# power.net
KiCad netlist of a schematic drawn in Altium Designer
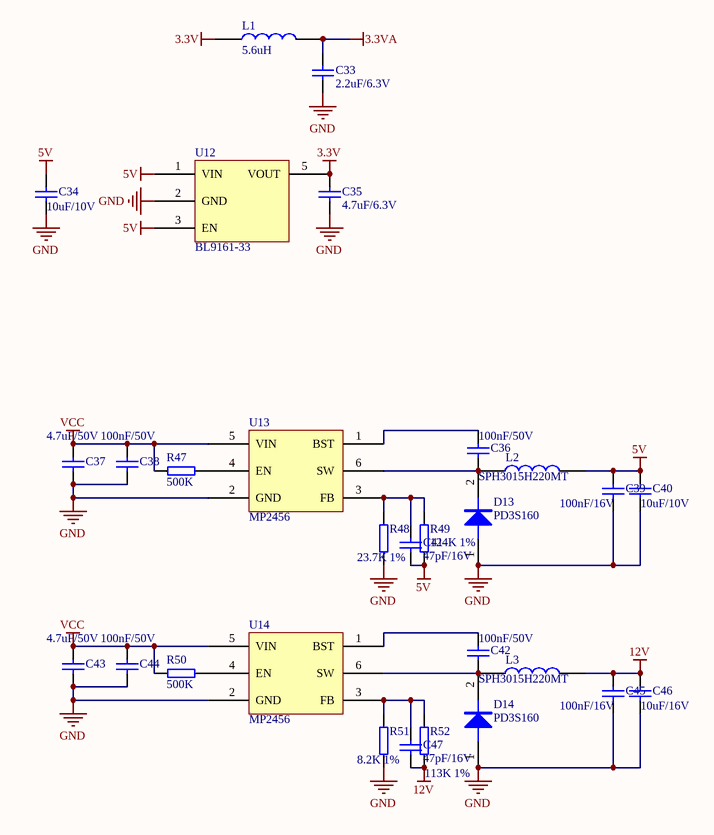
[diagram p0: power.SchDoc]

(export (version "E")
  (design (tool "Eeschema 10.0.6"))
  (components
    (comp (ref "C33") (value "2.2uF/6.3V") (footprint "C0402") (libsource (lib "zijianku") (part "cap")))
    (comp (ref "C34") (value "10uF/10V") (footprint "C0603") (libsource (lib "zijianku") (part "cap")))
    (comp (ref "C35") (value "4.7uF/6.3V") (footprint "C0603") (libsource (lib "zijianku") (part "cap")))
    (comp (ref "C36") (value "100nF/50V") (footprint "C0402") (libsource (lib "zijianku") (part "cap")))
    (comp (ref "C37") (value "4.7uF/50V") (footprint "C0603") (libsource (lib "zijianku") (part "cap")))
    (comp (ref "C38") (value "100nF/50V") (footprint "C0402") (libsource (lib "zijianku") (part "cap")))
    (comp (ref "C39") (value "100nF/16V") (footprint "C0402") (libsource (lib "zijianku") (part "cap")))
    (comp (ref "C40") (value "10uF/10V") (footprint "C0603") (libsource (lib "zijianku") (part "cap")))
    (comp (ref "C41") (value "47pF/16V") (footprint "C0402") (libsource (lib "zijianku") (part "cap")))
    (comp (ref "C42") (value "100nF/50V") (footprint "C0402") (libsource (lib "zijianku") (part "cap")))
    (comp (ref "C43") (value "4.7uF/50V") (footprint "C0603") (libsource (lib "zijianku") (part "cap")))
    (comp (ref "C44") (value "100nF/50V") (footprint "C0402") (libsource (lib "zijianku") (part "cap")))
    (comp (ref "C45") (value "100nF/16V") (footprint "C0402") (libsource (lib "zijianku") (part "cap")))
    (comp (ref "C46") (value "10uF/16V") (footprint "C0805") (libsource (lib "zijianku") (part "cap")))
    (comp (ref "C47") (value "47pF/16V") (footprint "C0402") (libsource (lib "zijianku") (part "cap")))
    (comp (ref "D13") (value "PD3S160") (footprint "POWERDI323") (libsource (lib "*") (part "DIODE")))
    (comp (ref "D14") (value "PD3S160") (footprint "POWERDI323") (libsource (lib "*") (part "DIODE")))
    (comp (ref "L1")
      (value "5.6uH")
      (footprint "L0402")
      (description "贴片电感")
      (libsource (lib "zijianku") (part "INDUCTOR"))
    )
    (comp (ref "L2")
      (value "SPH3015H220MT")
      (footprint "SPH3015")
      (description "顺络 22uH")
      (libsource (lib "zijianku") (part "INDUCTOR"))
    )
    (comp (ref "L3")
      (value "SPH3015H220MT")
      (footprint "SPH3015")
      (description "顺络 22uH")
      (libsource (lib "zijianku") (part "INDUCTOR"))
    )
    (comp (ref "R47") (value "500K") (footprint "R0402") (libsource (lib "zijianku") (part "Resistance")))
    (comp (ref "R48") (value "23.7K 1%") (footprint "R0402") (libsource (lib "zijianku") (part "Resistance")))
    (comp (ref "R49") (value "124K 1%") (footprint "R0402") (libsource (lib "zijianku") (part "Resistance")))
    (comp (ref "R50") (value "500K") (footprint "R0402") (libsource (lib "zijianku") (part "Resistance")))
    (comp (ref "R51") (value "8.2K 1%") (footprint "R0402") (libsource (lib "zijianku") (part "Resistance")))
    (comp (ref "R52") (value "113K 1%") (footprint "R0402") (libsource (lib "zijianku") (part "Resistance")))
    (comp (ref "U12")
      (value "BL9161-33")
      (footprint "SOT-23(5)")
      (libsource (lib "zijianku") (part "BL9161"))
    )
    (comp (ref "U13") (value "MP2456") (footprint "SOT-23(6)") (libsource (lib "zijianku") (part "MP2456")))
    (comp (ref "U14") (value "MP2456") (footprint "SOT-23(6)") (libsource (lib "zijianku") (part "MP2456")))
  )
  (nets
    (net (code "1") (name "3.3V") (class "Default")
      (node (ref "C35") (pin "2") (pinfunction "1_2") (pintype "passive"))
      (node (ref "L1") (pin "1") (pinfunction "1_1") (pintype "passive"))
      (node (ref "U12") (pin "5") (pinfunction "VOUT_5") (pintype "passive"))
    )
    (net (code "2") (name "3.3VA") (class "Default")
      (node (ref "C33") (pin "2") (pinfunction "1_2") (pintype "passive"))
      (node (ref "L1") (pin "2") (pinfunction "2_2") (pintype "passive"))
    )
    (net (code "3") (name "5V") (class "Default")
      (node (ref "C34") (pin "2") (pinfunction "1_2") (pintype "passive"))
      (node (ref "C39") (pin "2") (pinfunction "1_2") (pintype "passive"))
      (node (ref "C40") (pin "2") (pinfunction "1_2") (pintype "passive"))
      (node (ref "C41") (pin "2") (pinfunction "1_2") (pintype "passive"))
      (node (ref "L2") (pin "2") (pinfunction "2_2") (pintype "passive"))
      (node (ref "R49") (pin "1") (pintype "passive"))
      (node (ref "U12") (pin "1") (pinfunction "VIN_1") (pintype "passive"))
      (node (ref "U12") (pin "3") (pinfunction "EN_3") (pintype "passive"))
    )
    (net (code "4") (name "12V") (class "Default")
      (node (ref "C45") (pin "2") (pinfunction "1_2") (pintype "passive"))
      (node (ref "C46") (pin "2") (pinfunction "1_2") (pintype "passive"))
      (node (ref "C47") (pin "2") (pinfunction "1_2") (pintype "passive"))
      (node (ref "L3") (pin "2") (pinfunction "2_2") (pintype "passive"))
      (node (ref "R52") (pin "1") (pintype "passive"))
    )
    (net (code "5") (name "GND") (class "Default")
      (node (ref "C33") (pin "1") (pinfunction "0_1") (pintype "passive"))
      (node (ref "C34") (pin "1") (pinfunction "0_1") (pintype "passive"))
      (node (ref "C35") (pin "1") (pinfunction "0_1") (pintype "passive"))
      (node (ref "C37") (pin "1") (pinfunction "0_1") (pintype "passive"))
      (node (ref "C38") (pin "1") (pinfunction "0_1") (pintype "passive"))
      (node (ref "C39") (pin "1") (pinfunction "0_1") (pintype "passive"))
      (node (ref "C40") (pin "1") (pinfunction "0_1") (pintype "passive"))
      (node (ref "C43") (pin "1") (pinfunction "0_1") (pintype "passive"))
      (node (ref "C44") (pin "1") (pinfunction "0_1") (pintype "passive"))
      (node (ref "C45") (pin "1") (pinfunction "0_1") (pintype "passive"))
      (node (ref "C46") (pin "1") (pinfunction "0_1") (pintype "passive"))
      (node (ref "D13") (pin "1") (pinfunction "A_1") (pintype "passive"))
      (node (ref "D14") (pin "1") (pinfunction "A_1") (pintype "passive"))
      (node (ref "R48") (pin "1") (pintype "passive"))
      (node (ref "R51") (pin "1") (pintype "passive"))
      (node (ref "U12") (pin "2") (pinfunction "GND_2") (pintype "passive"))
      (node (ref "U13") (pin "2") (pinfunction "GND_2") (pintype "passive"))
      (node (ref "U14") (pin "2") (pinfunction "GND_2") (pintype "passive"))
    )
    (net (code "6") (name "Net-(C36-0)") (class "Default")
      (node (ref "C36") (pin "1") (pinfunction "0_1") (pintype "passive"))
      (node (ref "U13") (pin "1") (pinfunction "BST_1") (pintype "passive"))
    )
    (net (code "7") (name "Net-(C36-1)") (class "Default")
      (node (ref "C36") (pin "2") (pinfunction "1_2") (pintype "passive"))
      (node (ref "D13") (pin "2") (pinfunction "K_2") (pintype "passive"))
      (node (ref "L2") (pin "1") (pinfunction "1_1") (pintype "passive"))
      (node (ref "U13") (pin "6") (pinfunction "SW_6") (pintype "passive"))
    )
    (net (code "8") (name "Net-(C41-0)") (class "Default")
      (node (ref "C41") (pin "1") (pinfunction "0_1") (pintype "passive"))
      (node (ref "R48") (pin "2") (pintype "passive"))
      (node (ref "R49") (pin "2") (pintype "passive"))
      (node (ref "U13") (pin "3") (pinfunction "FB_3") (pintype "passive"))
    )
    (net (code "9") (name "Net-(C42-0)") (class "Default")
      (node (ref "C42") (pin "1") (pinfunction "0_1") (pintype "passive"))
      (node (ref "U14") (pin "1") (pinfunction "BST_1") (pintype "passive"))
    )
    (net (code "10") (name "Net-(C42-1)") (class "Default")
      (node (ref "C42") (pin "2") (pinfunction "1_2") (pintype "passive"))
      (node (ref "D14") (pin "2") (pinfunction "K_2") (pintype "passive"))
      (node (ref "L3") (pin "1") (pinfunction "1_1") (pintype "passive"))
      (node (ref "U14") (pin "6") (pinfunction "SW_6") (pintype "passive"))
    )
    (net (code "11") (name "Net-(C47-0)") (class "Default")
      (node (ref "C47") (pin "1") (pinfunction "0_1") (pintype "passive"))
      (node (ref "R51") (pin "2") (pintype "passive"))
      (node (ref "R52") (pin "2") (pintype "passive"))
      (node (ref "U14") (pin "3") (pinfunction "FB_3") (pintype "passive"))
    )
    (net (code "12") (name "Net-(U13-EN)") (class "Default")
      (node (ref "R47") (pin "2") (pintype "passive"))
      (node (ref "U13") (pin "4") (pinfunction "EN_4") (pintype "passive"))
    )
    (net (code "13") (name "Net-(U14-EN)") (class "Default")
      (node (ref "R50") (pin "2") (pintype "passive"))
      (node (ref "U14") (pin "4") (pinfunction "EN_4") (pintype "passive"))
    )
    (net (code "14") (name "VCC") (class "Default")
      (node (ref "C37") (pin "2") (pinfunction "1_2") (pintype "passive"))
      (node (ref "C38") (pin "2") (pinfunction "1_2") (pintype "passive"))
      (node (ref "C43") (pin "2") (pinfunction "1_2") (pintype "passive"))
      (node (ref "C44") (pin "2") (pinfunction "1_2") (pintype "passive"))
      (node (ref "R47") (pin "1") (pintype "passive"))
      (node (ref "R50") (pin "1") (pintype "passive"))
      (node (ref "U13") (pin "5") (pinfunction "VIN_5") (pintype "passive"))
      (node (ref "U14") (pin "5") (pinfunction "VIN_5") (pintype "passive"))
    )
  )
)
